# SIM4G_EC200S.net
KiCad netlist of a schematic drawn in Altium Designer
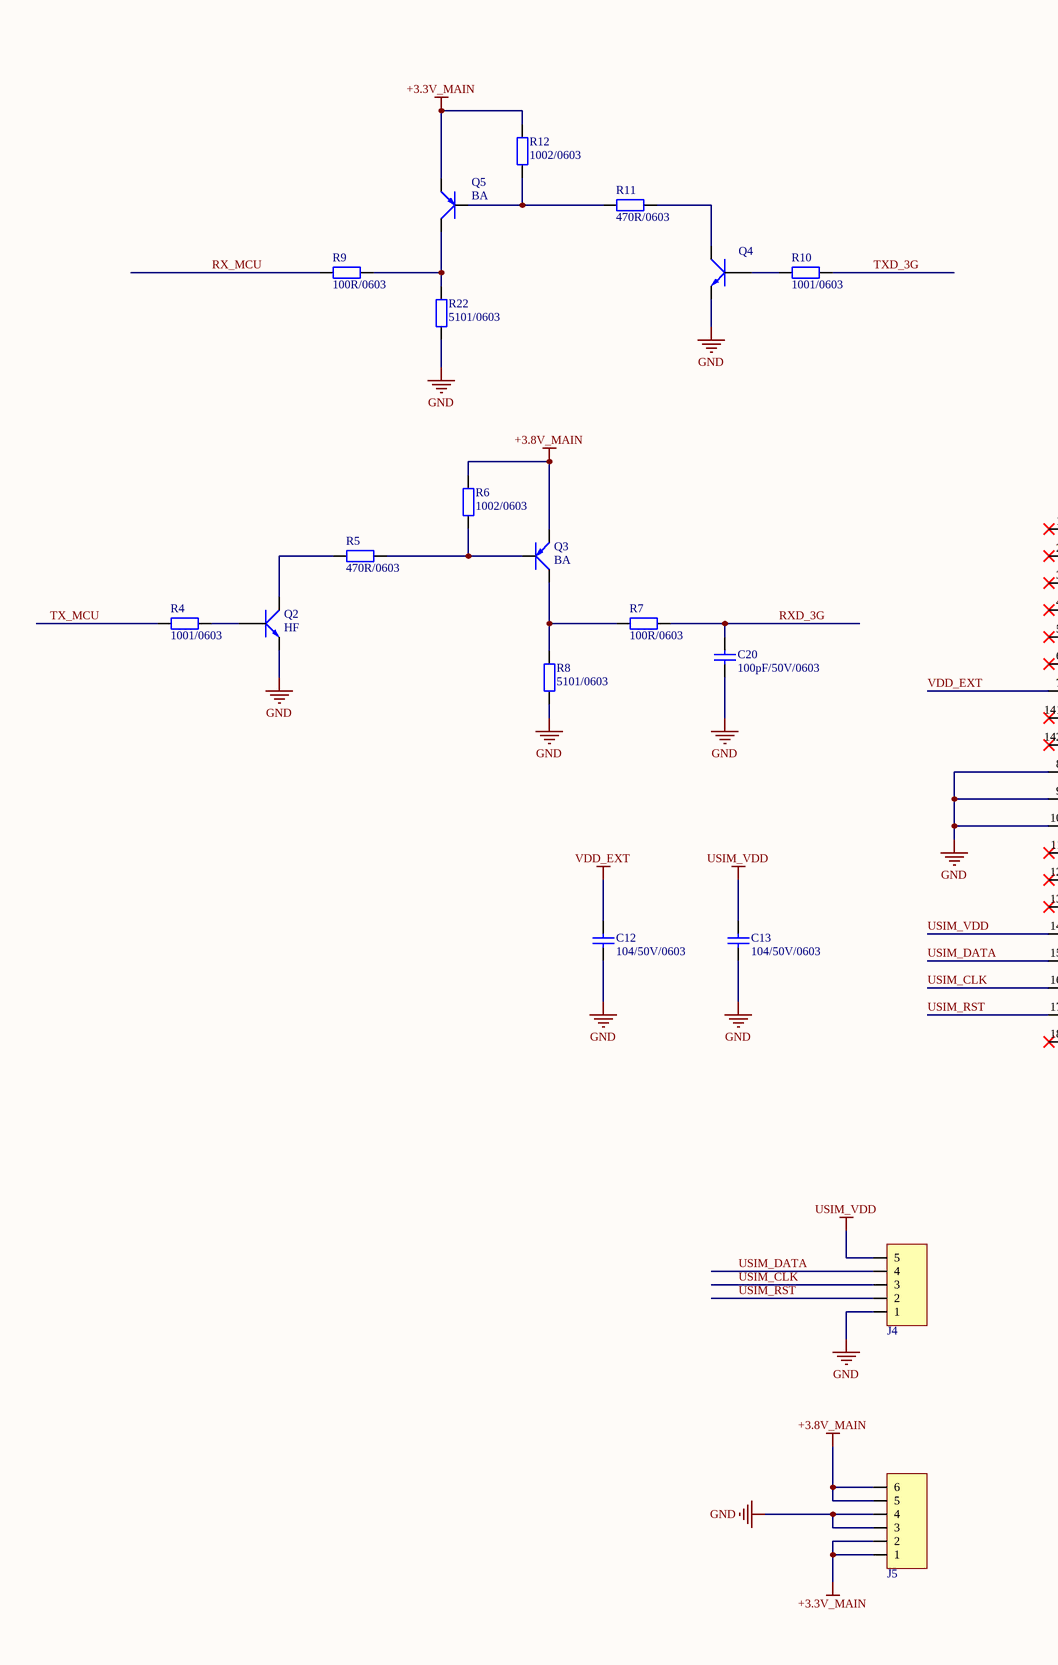
[diagram p0: SIM4G_EC200S.SchDoc, left]
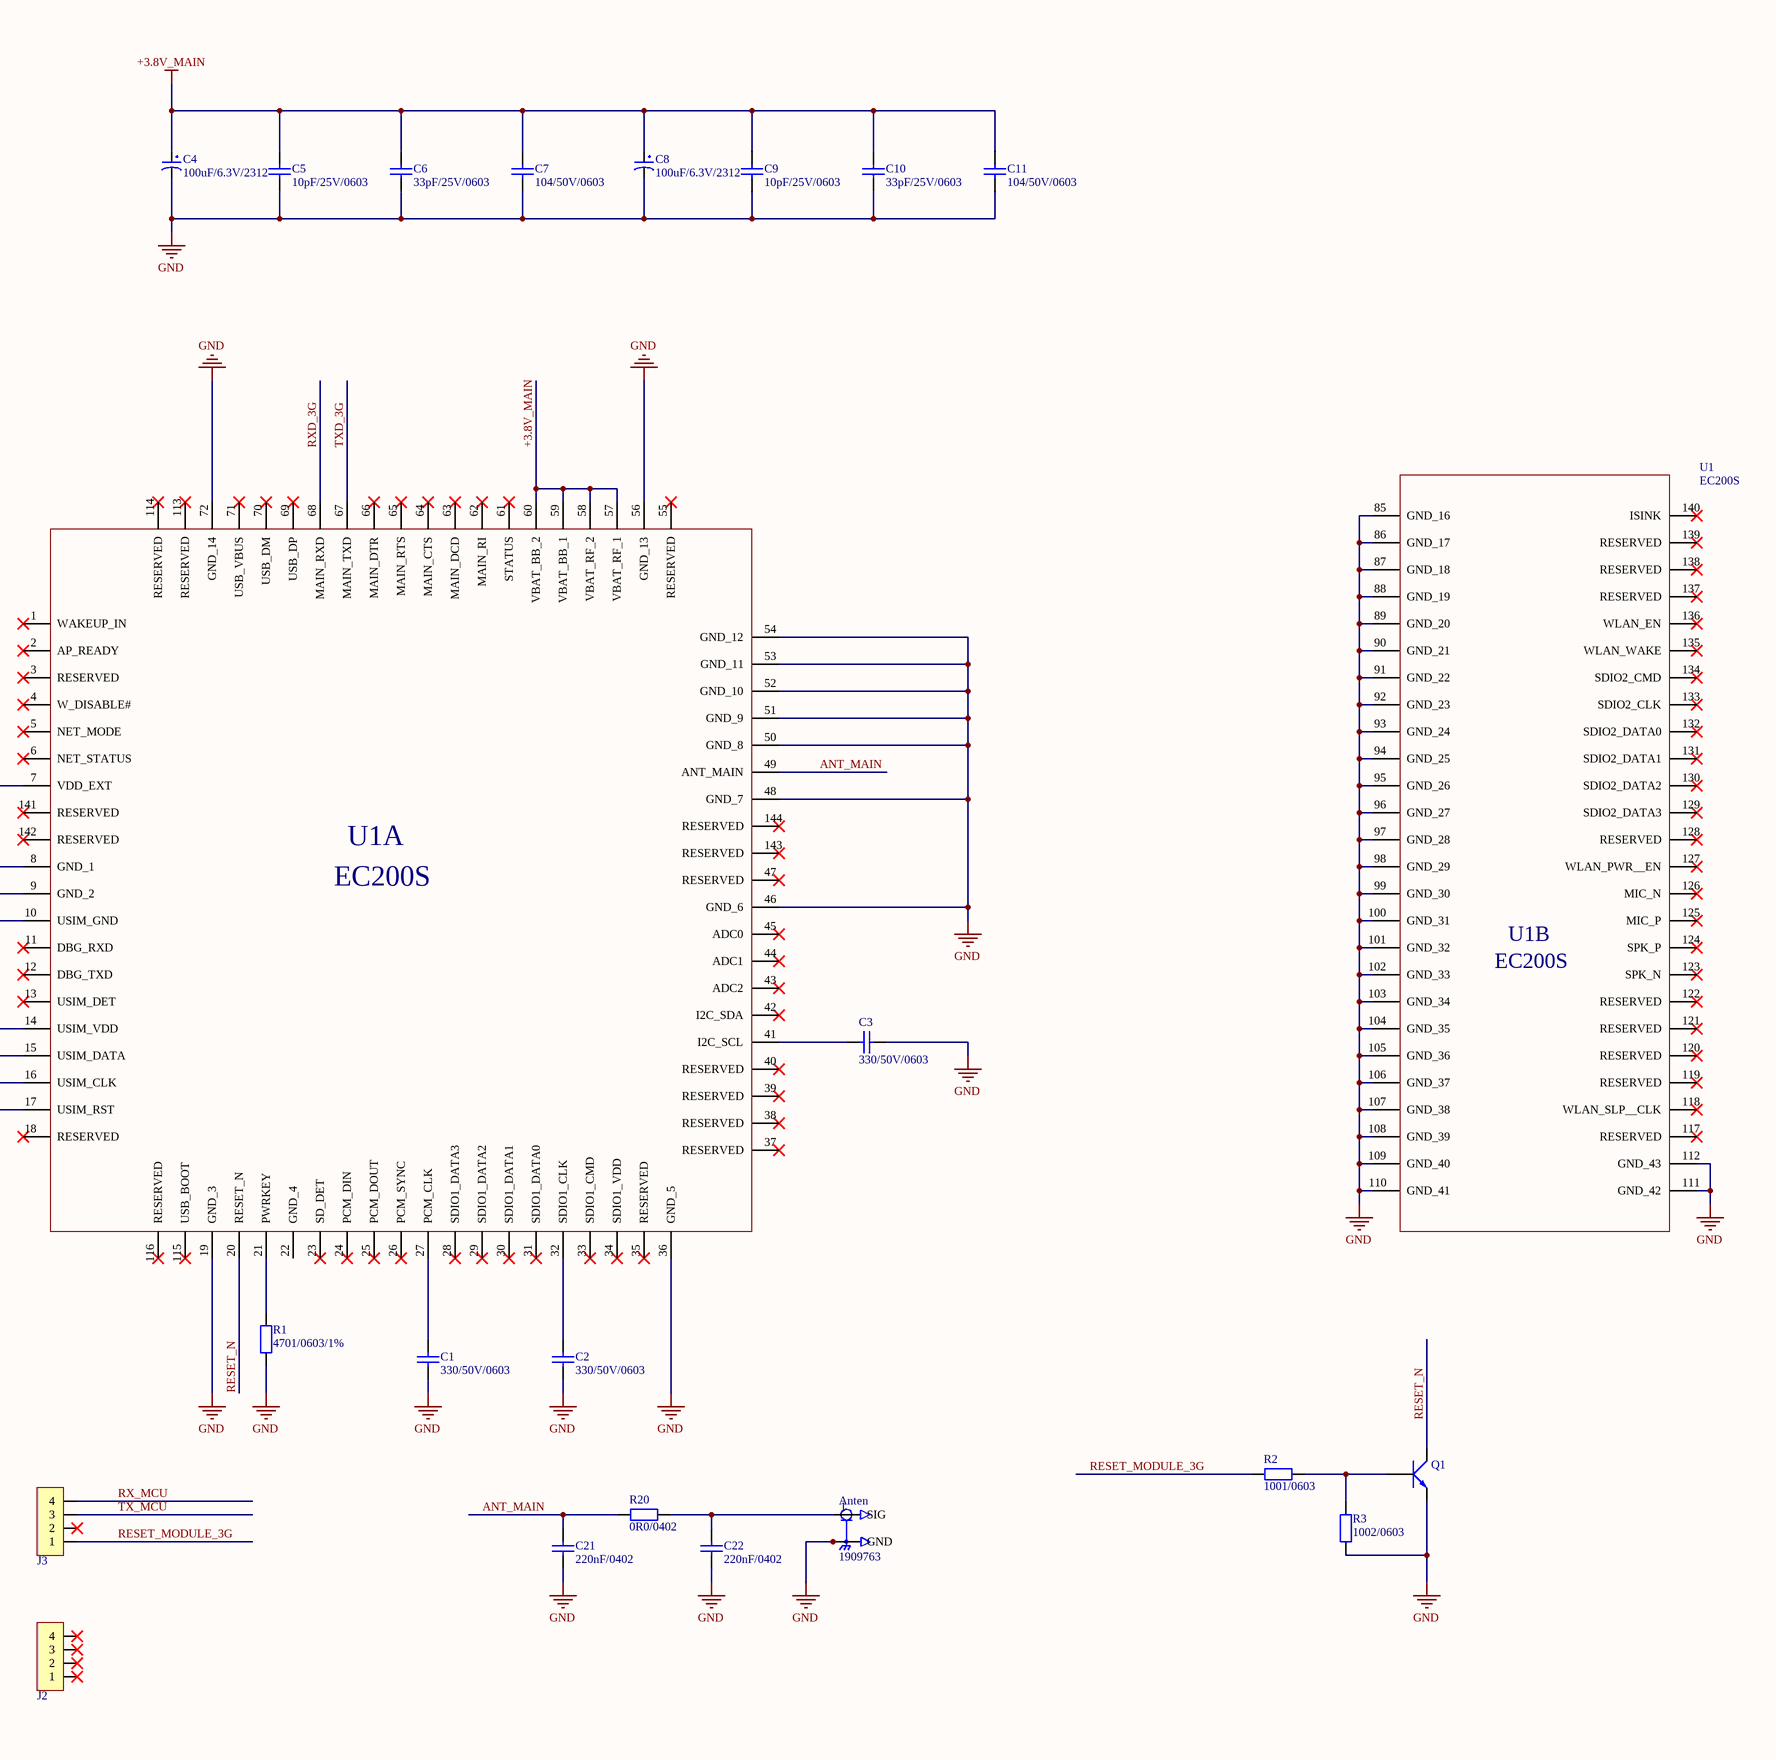
[diagram p1: SIM4G_EC200S.SchDoc, right]

(export (version "E")
  (design (tool "Eeschema 10.0.6"))
  (components
    (comp (ref "Anten")
      (value "1909763")
      (footprint "TE_1909763-1")
      (description "VAO ITEM, MINI RF HEADER")
      (fields (field (name "MP") "1909763-1"))
      (libsource (lib "Labrary_Tu_Nguon_Version2") (part "Antenna"))
    )
    (comp (ref "C1")
      (value "330/50V/0603")
      (footprint "tu 0603")
      (description "Dán")
      (libsource (lib "Altium_Lib_by_KhueNguyenCreator") (part "Tu 0603 563 16V 10%"))
    )
    (comp (ref "C2")
      (value "330/50V/0603")
      (footprint "tu 0603")
      (description "Dán")
      (libsource (lib "Altium_Lib_by_KhueNguyenCreator") (part "Tu 0603 563 16V 10%"))
    )
    (comp (ref "C3")
      (value "330/50V/0603")
      (footprint "tu 0603")
      (description "Dán")
      (libsource (lib "Altium_Lib_by_KhueNguyenCreator") (part "Tu 0603 563 16V 10%"))
    )
    (comp (ref "C4")
      (value "100uF/6.3V/2312")
      (footprint "tu tantalum smd3216")
      (description "Dán")
      (libsource (lib "Altium_Lib_by_KhueNguyenCreator") (part "Tu tantalum 10uF 16V SMD3216"))
    )
    (comp (ref "C5")
      (value "10pF/25V/0603")
      (footprint "tu 0603")
      (description "Dán")
      (libsource (lib "Altium_Lib_by_KhueNguyenCreator") (part "Tu 0603 563 16V 10%"))
    )
    (comp (ref "C6")
      (value "33pF/25V/0603")
      (footprint "tu 0603")
      (description "Dán")
      (libsource (lib "Altium_Lib_by_KhueNguyenCreator") (part "Tu 0603 563 16V 10%"))
    )
    (comp (ref "C7")
      (value "104/50V/0603")
      (footprint "tu 0603")
      (description "Dán")
      (libsource (lib "Altium_Lib_by_KhueNguyenCreator") (part "Tu 0603 563 16V 10%"))
    )
    (comp (ref "C8")
      (value "100uF/6.3V/2312")
      (footprint "tu tantalum smd3216")
      (description "Dán")
      (libsource (lib "Altium_Lib_by_KhueNguyenCreator") (part "Tu tantalum 10uF 16V SMD3216"))
    )
    (comp (ref "C9")
      (value "10pF/25V/0603")
      (footprint "tu 0603")
      (description "Dán")
      (libsource (lib "Altium_Lib_by_KhueNguyenCreator") (part "Tu 0603 563 16V 10%"))
    )
    (comp (ref "C10")
      (value "33pF/25V/0603")
      (footprint "tu 0603")
      (description "Dán")
      (libsource (lib "Altium_Lib_by_KhueNguyenCreator") (part "Tu 0603 563 16V 10%"))
    )
    (comp (ref "C11")
      (value "104/50V/0603")
      (footprint "tu 0603")
      (description "Dán")
      (libsource (lib "Altium_Lib_by_KhueNguyenCreator") (part "Tu 0603 563 16V 10%"))
    )
    (comp (ref "C12")
      (value "104/50V/0603")
      (footprint "tu 0603")
      (description "Dán")
      (libsource (lib "Altium_Lib_by_KhueNguyenCreator") (part "Tu 0603 563 16V 10%"))
    )
    (comp (ref "C13")
      (value "104/50V/0603")
      (footprint "tu 0603")
      (description "Dán")
      (libsource (lib "Altium_Lib_by_KhueNguyenCreator") (part "Tu 0603 563 16V 10%"))
    )
    (comp (ref "C20")
      (value "100pF/50V/0603")
      (footprint "tu 0603")
      (description "Dán")
      (libsource (lib "Altium_Lib_by_KhueNguyenCreator") (part "Tu 0603 563 16V 10%"))
    )
    (comp (ref "C21")
      (value "220nF/0402")
      (footprint "tu 0402")
      (description "Dán")
      (libsource (lib "Altium_Lib_by_KhueNguyenCreator") (part "Tu 0402 220nF 6.3V 20%"))
    )
    (comp (ref "C22")
      (value "220nF/0402")
      (footprint "tu 0402")
      (description "Dán")
      (libsource (lib "Altium_Lib_by_KhueNguyenCreator") (part "Tu 0402 220nF 6.3V 20%"))
    )
    (comp (ref "J2")
      (value "JP 1x4 2.54")
      (footprint "JP 1x4 DT")
      (description "Cắm")
      (libsource (lib "Altium_Lib_by_KhueNguyenCreator") (part "JP 1x4 2.54 Duc Thang"))
    )
    (comp (ref "J3")
      (value "JP 1x4 2.54")
      (footprint "JP 1x4 DT")
      (description "Cắm")
      (libsource (lib "Altium_Lib_by_KhueNguyenCreator") (part "JP 1x4 2.54 Duc Thang"))
    )
    (comp (ref "J4")
      (value "JP 1x5 2.54")
      (footprint "JP 1x5 DT")
      (description "Cắm")
      (libsource (lib "Altium_Lib_by_KhueNguyenCreator") (part "JP 1x5 2.54 Duc Thang"))
    )
    (comp (ref "J5")
      (value "JP 1x6 2.54")
      (footprint "JP 1x6 DT")
      (description "Cắm")
      (libsource (lib "Altium_Lib_by_KhueNguyenCreator") (part "JP 1x6 2.54 Duc Thang"))
    )
    (comp (ref "Q1")
      (value "HF")
      (footprint "SOT23")
      (description "NPN transistor")
      (libsource (lib "Altium_Lib_by_KhueNguyenCreator") (part "C1815 HF SMD"))
    )
    (comp (ref "Q2")
      (value "HF")
      (footprint "SOT23")
      (description "NPN transistor")
      (libsource (lib "Altium_Lib_by_KhueNguyenCreator") (part "C1815 HF SMD"))
    )
    (comp (ref "Q3")
      (value "BA")
      (footprint "SOT23")
      (description "PMBT3906,235\r\nMMBT4403/SOT_0")
      (libsource (lib "Altium_Lib_by_KhueNguyenCreator") (part "A1015 BA SMD"))
    )
    (comp (ref "Q4")
      (value "HF")
      (footprint "SOT23")
      (description "NPN transistor")
      (libsource (lib "Altium_Lib_by_KhueNguyenCreator") (part "C1815 HF SMD"))
    )
    (comp (ref "Q5")
      (value "BA")
      (footprint "SOT23")
      (description "PNP 600mW, ECB")
      (libsource (lib "Altium_Lib_by_KhueNguyenCreator") (part "A1015 BA SMD"))
    )
    (comp (ref "R1")
      (value "4701/0603/1%")
      (footprint "tro smd 0603")
      (description "Dán")
      (libsource (lib "Altium_Lib_by_KhueNguyenCreator") (part "Tro 0603 5% 510R"))
    )
    (comp (ref "R2")
      (value "1001/0603")
      (footprint "tro smd 0603")
      (description "Dán")
      (libsource (lib "Altium_Lib_by_KhueNguyenCreator") (part "Tro 0603 5% 510R"))
    )
    (comp (ref "R3")
      (value "1002/0603")
      (footprint "tro smd 0603")
      (description "Dán")
      (libsource (lib "Altium_Lib_by_KhueNguyenCreator") (part "Tro 0603 5% 510R"))
    )
    (comp (ref "R4")
      (value "1001/0603")
      (footprint "tro smd 0603")
      (description "Dán")
      (libsource (lib "Altium_Lib_by_KhueNguyenCreator") (part "Tro 0603 5% 510R"))
    )
    (comp (ref "R5")
      (value "470R/0603")
      (footprint "tro smd 0603")
      (description "Dán")
      (libsource (lib "Altium_Lib_by_KhueNguyenCreator") (part "Tro 0603 5% 510R"))
    )
    (comp (ref "R6")
      (value "1002/0603")
      (footprint "tro smd 0603")
      (description "Dán")
      (libsource (lib "Altium_Lib_by_KhueNguyenCreator") (part "Tro 0603 5% 510R"))
    )
    (comp (ref "R7")
      (value "100R/0603")
      (footprint "tro smd 0603")
      (description "Dán")
      (libsource (lib "Altium_Lib_by_KhueNguyenCreator") (part "Tro 0603 5% 510R"))
    )
    (comp (ref "R8")
      (value "5101/0603")
      (footprint "tro smd 0603")
      (description "Dán")
      (libsource (lib "Altium_Lib_by_KhueNguyenCreator") (part "Tro 0603 5% 510R"))
    )
    (comp (ref "R9")
      (value "100R/0603")
      (footprint "tro smd 0603")
      (description "Dán")
      (libsource (lib "Altium_Lib_by_KhueNguyenCreator") (part "Tro 0603 5% 510R"))
    )
    (comp (ref "R10")
      (value "1001/0603")
      (footprint "tro smd 0603")
      (description "Dán")
      (libsource (lib "Altium_Lib_by_KhueNguyenCreator") (part "Tro 0603 5% 510R"))
    )
    (comp (ref "R11")
      (value "470R/0603")
      (footprint "tro smd 0603")
      (description "Dán")
      (libsource (lib "Altium_Lib_by_KhueNguyenCreator") (part "Tro 0603 5% 510R"))
    )
    (comp (ref "R12")
      (value "1002/0603")
      (footprint "tro smd 0603")
      (description "Dán")
      (libsource (lib "Altium_Lib_by_KhueNguyenCreator") (part "Tro 0603 5% 510R"))
    )
    (comp (ref "R20")
      (value "0R0/0402")
      (footprint "tro smd 0603")
      (description "Dán")
      (libsource (lib "Altium_Lib_by_KhueNguyenCreator") (part "Tro 0603 5% 510R"))
    )
    (comp (ref "R22")
      (value "5101/0603")
      (footprint "tro smd 0603")
      (description "Dán")
      (libsource (lib "Altium_Lib_by_KhueNguyenCreator") (part "Tro 0603 5% 510R"))
    )
    (comp (ref "U1")
      (value "EC200S")
      (footprint "EC200U")
      (description "GMS/4G-LTE")
      (libsource (lib "Labrary_Tu_Nguon_Version2") (part "EC200S"))
    )
  )
  (nets
    (net (code "1") (name "+3.3V_MAIN") (class "Default")
      (node (ref "J5") (pin "1") (pinfunction "1_1") (pintype "passive"))
      (node (ref "J5") (pin "2") (pinfunction "2_2") (pintype "passive"))
      (node (ref "Q5") (pin "2") (pinfunction "E_2") (pintype "passive"))
      (node (ref "R12") (pin "1") (pinfunction "1_1") (pintype "passive"))
    )
    (net (code "2") (name "+3.8V_MAIN") (class "Default")
      (node (ref "C10") (pin "1") (pinfunction "1_1") (pintype "passive"))
      (node (ref "C11") (pin "1") (pinfunction "1_1") (pintype "passive"))
      (node (ref "C4") (pin "1") (pinfunction "1_1") (pintype "passive"))
      (node (ref "C5") (pin "1") (pinfunction "1_1") (pintype "passive"))
      (node (ref "C6") (pin "1") (pinfunction "1_1") (pintype "passive"))
      (node (ref "C7") (pin "1") (pinfunction "1_1") (pintype "passive"))
      (node (ref "C8") (pin "1") (pinfunction "1_1") (pintype "passive"))
      (node (ref "C9") (pin "1") (pinfunction "1_1") (pintype "passive"))
      (node (ref "J5") (pin "5") (pinfunction "5_5") (pintype "passive"))
      (node (ref "J5") (pin "6") (pinfunction "6_6") (pintype "passive"))
      (node (ref "Q3") (pin "2") (pinfunction "E_2") (pintype "passive"))
      (node (ref "R6") (pin "1") (pinfunction "1_1") (pintype "passive"))
      (node (ref "U1") (pin "57") (pinfunction "VBAT_RF_1_57") (pintype "passive"))
      (node (ref "U1") (pin "58") (pinfunction "VBAT_RF_2_58") (pintype "passive"))
      (node (ref "U1") (pin "59") (pinfunction "VBAT_BB_1_59") (pintype "passive"))
      (node (ref "U1") (pin "60") (pinfunction "VBAT_BB_2_60") (pintype "passive"))
    )
    (net (code "3") (name "/ANT_MAIN") (class "Default")
      (node (ref "C21") (pin "2") (pinfunction "2_2") (pintype "passive"))
      (node (ref "R20") (pin "1") (pinfunction "1_1") (pintype "passive"))
      (node (ref "U1") (pin "49") (pinfunction "ANT_MAIN_49") (pintype "passive"))
    )
    (net (code "4") (name "/RESET_MODULE_3G") (class "Default")
      (node (ref "J3") (pin "1") (pinfunction "1_1") (pintype "passive"))
      (node (ref "R2") (pin "2") (pinfunction "2_2") (pintype "passive"))
    )
    (net (code "5") (name "/RESET_N") (class "Default")
      (node (ref "Q1") (pin "3") (pinfunction "C_3") (pintype "passive"))
      (node (ref "U1") (pin "20") (pinfunction "RESET_N_20") (pintype "passive"))
    )
    (net (code "6") (name "/RXD_3G") (class "Default")
      (node (ref "C20") (pin "1") (pinfunction "1_1") (pintype "passive"))
      (node (ref "R7") (pin "1") (pinfunction "1_1") (pintype "passive"))
      (node (ref "U1") (pin "68") (pinfunction "MAIN_RXD_68") (pintype "passive"))
    )
    (net (code "7") (name "/RX_MCU") (class "Default")
      (node (ref "J3") (pin "4") (pinfunction "4_4") (pintype "passive"))
      (node (ref "R9") (pin "1") (pinfunction "1_1") (pintype "passive"))
    )
    (net (code "8") (name "/TXD_3G") (class "Default")
      (node (ref "R10") (pin "2") (pinfunction "2_2") (pintype "passive"))
      (node (ref "U1") (pin "67") (pinfunction "MAIN_TXD_67") (pintype "passive"))
    )
    (net (code "9") (name "/TX_MCU") (class "Default")
      (node (ref "J3") (pin "3") (pinfunction "3_3") (pintype "passive"))
      (node (ref "R4") (pin "2") (pinfunction "2_2") (pintype "passive"))
    )
    (net (code "10") (name "/USIM_CLK") (class "Default")
      (node (ref "J4") (pin "3") (pinfunction "3_3") (pintype "passive"))
      (node (ref "U1") (pin "16") (pinfunction "USIM_CLK_16") (pintype "passive"))
    )
    (net (code "11") (name "/USIM_DATA") (class "Default")
      (node (ref "J4") (pin "4") (pinfunction "4_4") (pintype "passive"))
      (node (ref "U1") (pin "15") (pinfunction "USIM_DATA_15") (pintype "passive"))
    )
    (net (code "12") (name "/USIM_RST") (class "Default")
      (node (ref "J4") (pin "2") (pinfunction "2_2") (pintype "passive"))
      (node (ref "U1") (pin "17") (pinfunction "USIM_RST_17") (pintype "passive"))
    )
    (net (code "13") (name "GND") (class "Default")
      (node (ref "Anten") (pin "2") (pinfunction "GND_2") (pintype "passive"))
      (node (ref "Anten") (pin "3") (pinfunction "GND_3") (pintype "passive"))
      (node (ref "C1") (pin "2") (pinfunction "2_2") (pintype "passive"))
      (node (ref "C10") (pin "2") (pinfunction "2_2") (pintype "passive"))
      (node (ref "C11") (pin "2") (pinfunction "2_2") (pintype "passive"))
      (node (ref "C12") (pin "2") (pinfunction "2_2") (pintype "passive"))
      (node (ref "C13") (pin "2") (pinfunction "2_2") (pintype "passive"))
      (node (ref "C2") (pin "2") (pinfunction "2_2") (pintype "passive"))
      (node (ref "C20") (pin "2") (pinfunction "2_2") (pintype "passive"))
      (node (ref "C21") (pin "1") (pinfunction "1_1") (pintype "passive"))
      (node (ref "C22") (pin "1") (pinfunction "1_1") (pintype "passive"))
      (node (ref "C3") (pin "2") (pinfunction "2_2") (pintype "passive"))
      (node (ref "C4") (pin "2") (pinfunction "2_2") (pintype "passive"))
      (node (ref "C5") (pin "2") (pinfunction "2_2") (pintype "passive"))
      (node (ref "C6") (pin "2") (pinfunction "2_2") (pintype "passive"))
      (node (ref "C7") (pin "2") (pinfunction "2_2") (pintype "passive"))
      (node (ref "C8") (pin "2") (pinfunction "2_2") (pintype "passive"))
      (node (ref "C9") (pin "2") (pinfunction "2_2") (pintype "passive"))
      (node (ref "J4") (pin "1") (pinfunction "1_1") (pintype "passive"))
      (node (ref "J5") (pin "3") (pinfunction "3_3") (pintype "passive"))
      (node (ref "J5") (pin "4") (pinfunction "4_4") (pintype "passive"))
      (node (ref "Q1") (pin "2") (pinfunction "E_2") (pintype "passive"))
      (node (ref "Q2") (pin "2") (pinfunction "E_2") (pintype "passive"))
      (node (ref "Q4") (pin "2") (pinfunction "E_2") (pintype "passive"))
      (node (ref "R1") (pin "1") (pinfunction "1_1") (pintype "passive"))
      (node (ref "R22") (pin "2") (pinfunction "2_2") (pintype "passive"))
      (node (ref "R3") (pin "2") (pinfunction "2_2") (pintype "passive"))
      (node (ref "R8") (pin "2") (pinfunction "2_2") (pintype "passive"))
      (node (ref "U1") (pin "10") (pinfunction "USIM_GND_10") (pintype "passive"))
      (node (ref "U1") (pin "100") (pinfunction "GND_31_100") (pintype "passive"))
      (node (ref "U1") (pin "101") (pinfunction "GND_32_101") (pintype "passive"))
      (node (ref "U1") (pin "102") (pinfunction "GND_33_102") (pintype "passive"))
      (node (ref "U1") (pin "103") (pinfunction "GND_34_103") (pintype "passive"))
      (node (ref "U1") (pin "104") (pinfunction "GND_35_104") (pintype "passive"))
      (node (ref "U1") (pin "105") (pinfunction "GND_36_105") (pintype "passive"))
      (node (ref "U1") (pin "106") (pinfunction "GND_37_106") (pintype "passive"))
      (node (ref "U1") (pin "107") (pinfunction "GND_38_107") (pintype "passive"))
      (node (ref "U1") (pin "108") (pinfunction "GND_39_108") (pintype "passive"))
      (node (ref "U1") (pin "109") (pinfunction "GND_40_109") (pintype "passive"))
      (node (ref "U1") (pin "110") (pinfunction "GND_41_110") (pintype "passive"))
      (node (ref "U1") (pin "111") (pinfunction "GND_42_111") (pintype "passive"))
      (node (ref "U1") (pin "112") (pinfunction "GND_43_112") (pintype "passive"))
      (node (ref "U1") (pin "19") (pinfunction "GND_3_19") (pintype "passive"))
      (node (ref "U1") (pin "36") (pinfunction "GND_5_36") (pintype "passive"))
      (node (ref "U1") (pin "46") (pinfunction "GND_6_46") (pintype "passive"))
      (node (ref "U1") (pin "48") (pinfunction "GND_7_48") (pintype "passive"))
      (node (ref "U1") (pin "50") (pinfunction "GND_8_50") (pintype "passive"))
      (node (ref "U1") (pin "51") (pinfunction "GND_9_51") (pintype "passive"))
      (node (ref "U1") (pin "52") (pinfunction "GND_10_52") (pintype "passive"))
      (node (ref "U1") (pin "53") (pinfunction "GND_11_53") (pintype "passive"))
      (node (ref "U1") (pin "54") (pinfunction "GND_12_54") (pintype "passive"))
      (node (ref "U1") (pin "56") (pinfunction "GND_13_56") (pintype "passive"))
      (node (ref "U1") (pin "72") (pinfunction "GND_14_72") (pintype "passive"))
      (node (ref "U1") (pin "8") (pinfunction "GND_1_8") (pintype "passive"))
      (node (ref "U1") (pin "85") (pinfunction "GND_16_85") (pintype "passive"))
      (node (ref "U1") (pin "86") (pinfunction "GND_17_86") (pintype "passive"))
      (node (ref "U1") (pin "87") (pinfunction "GND_18_87") (pintype "passive"))
      (node (ref "U1") (pin "88") (pinfunction "GND_19_88") (pintype "passive"))
      (node (ref "U1") (pin "89") (pinfunction "GND_20_89") (pintype "passive"))
      (node (ref "U1") (pin "9") (pinfunction "GND_2_9") (pintype "passive"))
      (node (ref "U1") (pin "90") (pinfunction "GND_21_90") (pintype "passive"))
      (node (ref "U1") (pin "91") (pinfunction "GND_22_91") (pintype "passive"))
      (node (ref "U1") (pin "92") (pinfunction "GND_23_92") (pintype "passive"))
      (node (ref "U1") (pin "93") (pinfunction "GND_24_93") (pintype "passive"))
      (node (ref "U1") (pin "94") (pinfunction "GND_25_94") (pintype "passive"))
      (node (ref "U1") (pin "95") (pinfunction "GND_26_95") (pintype "passive"))
      (node (ref "U1") (pin "96") (pinfunction "GND_27_96") (pintype "passive"))
      (node (ref "U1") (pin "97") (pinfunction "GND_28_97") (pintype "passive"))
      (node (ref "U1") (pin "98") (pinfunction "GND_29_98") (pintype "passive"))
      (node (ref "U1") (pin "99") (pinfunction "GND_30_99") (pintype "passive"))
    )
    (net (code "14") (name "Net-(Anten-SIG)") (class "Default")
      (node (ref "Anten") (pin "1") (pinfunction "SIG_1") (pintype "passive"))
      (node (ref "C22") (pin "2") (pinfunction "2_2") (pintype "passive"))
      (node (ref "R20") (pin "2") (pinfunction "2_2") (pintype "passive"))
    )
    (net (code "15") (name "Net-(Q1-B)") (class "Default")
      (node (ref "Q1") (pin "1") (pinfunction "B_1") (pintype "passive"))
      (node (ref "R2") (pin "1") (pinfunction "1_1") (pintype "passive"))
      (node (ref "R3") (pin "1") (pinfunction "1_1") (pintype "passive"))
    )
    (net (code "16") (name "Net-(Q2-B)") (class "Default")
      (node (ref "Q2") (pin "1") (pinfunction "B_1") (pintype "passive"))
      (node (ref "R4") (pin "1") (pinfunction "1_1") (pintype "passive"))
    )
    (net (code "17") (name "Net-(Q2-C)") (class "Default")
      (node (ref "Q2") (pin "3") (pinfunction "C_3") (pintype "passive"))
      (node (ref "R5") (pin "2") (pinfunction "2_2") (pintype "passive"))
    )
    (net (code "18") (name "Net-(Q3-B)") (class "Default")
      (node (ref "Q3") (pin "1") (pinfunction "B_1") (pintype "passive"))
      (node (ref "R5") (pin "1") (pinfunction "1_1") (pintype "passive"))
      (node (ref "R6") (pin "2") (pinfunction "2_2") (pintype "passive"))
    )
    (net (code "19") (name "Net-(Q3-C)") (class "Default")
      (node (ref "Q3") (pin "3") (pinfunction "C_3") (pintype "passive"))
      (node (ref "R7") (pin "2") (pinfunction "2_2") (pintype "passive"))
      (node (ref "R8") (pin "1") (pinfunction "1_1") (pintype "passive"))
    )
    (net (code "20") (name "Net-(Q4-B)") (class "Default")
      (node (ref "Q4") (pin "1") (pinfunction "B_1") (pintype "passive"))
      (node (ref "R10") (pin "1") (pinfunction "1_1") (pintype "passive"))
    )
    (net (code "21") (name "Net-(Q4-C)") (class "Default")
      (node (ref "Q4") (pin "3") (pinfunction "C_3") (pintype "passive"))
      (node (ref "R11") (pin "2") (pinfunction "2_2") (pintype "passive"))
    )
    (net (code "22") (name "Net-(Q5-B)") (class "Default")
      (node (ref "Q5") (pin "1") (pinfunction "B_1") (pintype "passive"))
      (node (ref "R11") (pin "1") (pinfunction "1_1") (pintype "passive"))
      (node (ref "R12") (pin "2") (pinfunction "2_2") (pintype "passive"))
    )
    (net (code "23") (name "Net-(Q5-C)") (class "Default")
      (node (ref "Q5") (pin "3") (pinfunction "C_3") (pintype "passive"))
      (node (ref "R22") (pin "1") (pinfunction "1_1") (pintype "passive"))
      (node (ref "R9") (pin "2") (pinfunction "2_2") (pintype "passive"))
    )
    (net (code "24") (name "Net-(U1-I2C_SCL)") (class "Default")
      (node (ref "C3") (pin "1") (pinfunction "1_1") (pintype "passive"))
      (node (ref "U1") (pin "41") (pinfunction "I2C_SCL_41") (pintype "passive"))
    )
    (net (code "25") (name "Net-(U1-PCM_CLK)") (class "Default")
      (node (ref "C1") (pin "1") (pinfunction "1_1") (pintype "passive"))
      (node (ref "U1") (pin "27") (pinfunction "PCM_CLK_27") (pintype "passive"))
    )
    (net (code "26") (name "Net-(U1-PWRKEY)") (class "Default")
      (node (ref "R1") (pin "2") (pinfunction "2_2") (pintype "passive"))
      (node (ref "U1") (pin "21") (pinfunction "PWRKEY_21") (pintype "passive"))
    )
    (net (code "27") (name "Net-(U1-SDIO1_CLK)") (class "Default")
      (node (ref "C2") (pin "1") (pinfunction "1_1") (pintype "passive"))
      (node (ref "U1") (pin "32") (pinfunction "SDIO1_CLK_32") (pintype "passive"))
    )
    (net (code "28") (name "USIM_VDD") (class "Default")
      (node (ref "C13") (pin "1") (pinfunction "1_1") (pintype "passive"))
      (node (ref "J4") (pin "5") (pinfunction "5_5") (pintype "passive"))
      (node (ref "U1") (pin "14") (pinfunction "USIM_VDD_14") (pintype "passive"))
    )
    (net (code "29") (name "VDD_EXT") (class "Default")
      (node (ref "C12") (pin "1") (pinfunction "1_1") (pintype "passive"))
      (node (ref "U1") (pin "7") (pinfunction "VDD_EXT_7") (pintype "passive"))
    )
    (net (code "30") (name "unconnected-(J2-Pad1)") (class "Default")
      (node (ref "J2") (pin "1") (pinfunction "1_1") (pintype "passive+no_connect"))
    )
    (net (code "31") (name "unconnected-(J2-Pad2)") (class "Default")
      (node (ref "J2") (pin "2") (pinfunction "2_2") (pintype "passive+no_connect"))
    )
    (net (code "32") (name "unconnected-(J2-Pad3)") (class "Default")
      (node (ref "J2") (pin "3") (pinfunction "3_3") (pintype "passive+no_connect"))
    )
    (net (code "33") (name "unconnected-(J2-Pad4)") (class "Default")
      (node (ref "J2") (pin "4") (pinfunction "4_4") (pintype "passive+no_connect"))
    )
    (net (code "34") (name "unconnected-(J3-Pad2)") (class "Default")
      (node (ref "J3") (pin "2") (pinfunction "2_2") (pintype "passive+no_connect"))
    )
    (net (code "35") (name "unconnected-(U1-ADC0-Pad45)") (class "Default")
      (node (ref "U1") (pin "45") (pinfunction "ADC0_45") (pintype "passive+no_connect"))
    )
    (net (code "36") (name "unconnected-(U1-ADC1-Pad44)") (class "Default")
      (node (ref "U1") (pin "44") (pinfunction "ADC1_44") (pintype "passive+no_connect"))
    )
    (net (code "37") (name "unconnected-(U1-ADC2-Pad43)") (class "Default")
      (node (ref "U1") (pin "43") (pinfunction "ADC2_43") (pintype "passive+no_connect"))
    )
    (net (code "38") (name "unconnected-(U1-AP_READY-Pad2)") (class "Default")
      (node (ref "U1") (pin "2") (pinfunction "AP_READY_2") (pintype "passive+no_connect"))
    )
    (net (code "39") (name "unconnected-(U1-DBG_RXD-Pad11)") (class "Default")
      (node (ref "U1") (pin "11") (pinfunction "DBG_RXD_11") (pintype "passive+no_connect"))
    )
    (net (code "40") (name "unconnected-(U1-DBG_TXD-Pad12)") (class "Default")
      (node (ref "U1") (pin "12") (pinfunction "DBG_TXD_12") (pintype "passive+no_connect"))
    )
    (net (code "41") (name "unconnected-(U1-GND_4-Pad22)") (class "Default")
      (node (ref "U1") (pin "22") (pinfunction "GND_4_22") (pintype "passive"))
    )
    (net (code "42") (name "unconnected-(U1-I2C_SDA-Pad42)") (class "Default")
      (node (ref "U1") (pin "42") (pinfunction "I2C_SDA_42") (pintype "passive+no_connect"))
    )
    (net (code "43") (name "unconnected-(U1-ISINK-Pad140)") (class "Default")
      (node (ref "U1") (pin "140") (pinfunction "ISINK_140") (pintype "passive+no_connect"))
    )
    (net (code "44") (name "unconnected-(U1-MAIN_CTS-Pad64)") (class "Default")
      (node (ref "U1") (pin "64") (pinfunction "MAIN_CTS_64") (pintype "passive+no_connect"))
    )
    (net (code "45") (name "unconnected-(U1-MAIN_DCD-Pad63)") (class "Default")
      (node (ref "U1") (pin "63") (pinfunction "MAIN_DCD_63") (pintype "passive+no_connect"))
    )
    (net (code "46") (name "unconnected-(U1-MAIN_DTR-Pad66)") (class "Default")
      (node (ref "U1") (pin "66") (pinfunction "MAIN_DTR_66") (pintype "passive+no_connect"))
    )
    (net (code "47") (name "unconnected-(U1-MAIN_RI-Pad62)") (class "Default")
      (node (ref "U1") (pin "62") (pinfunction "MAIN_RI_62") (pintype "passive+no_connect"))
    )
    (net (code "48") (name "unconnected-(U1-MAIN_RTS-Pad65)") (class "Default")
      (node (ref "U1") (pin "65") (pinfunction "MAIN_RTS_65") (pintype "passive+no_connect"))
    )
    (net (code "49") (name "unconnected-(U1-MIC_N-Pad126)") (class "Default")
      (node (ref "U1") (pin "126") (pinfunction "MIC_N_126") (pintype "passive+no_connect"))
    )
    (net (code "50") (name "unconnected-(U1-MIC_P-Pad125)") (class "Default")
      (node (ref "U1") (pin "125") (pinfunction "MIC_P_125") (pintype "passive+no_connect"))
    )
    (net (code "51") (name "unconnected-(U1-NET_MODE-Pad5)") (class "Default")
      (node (ref "U1") (pin "5") (pinfunction "NET_MODE_5") (pintype "passive+no_connect"))
    )
    (net (code "52") (name "unconnected-(U1-NET_STATUS-Pad6)") (class "Default")
      (node (ref "U1") (pin "6") (pinfunction "NET_STATUS_6") (pintype "passive+no_connect"))
    )
    (net (code "53") (name "unconnected-(U1-PCM_DIN-Pad24)") (class "Default")
      (node (ref "U1") (pin "24") (pinfunction "PCM_DIN_24") (pintype "passive+no_connect"))
    )
    (net (code "54") (name "unconnected-(U1-PCM_DOUT-Pad25)") (class "Default")
      (node (ref "U1") (pin "25") (pinfunction "PCM_DOUT_25") (pintype "passive+no_connect"))
    )
    (net (code "55") (name "unconnected-(U1-PCM_SYNC-Pad26)") (class "Default")
      (node (ref "U1") (pin "26") (pinfunction "PCM_SYNC_26") (pintype "passive+no_connect"))
    )
    (net (code "56") (name "unconnected-(U1-RESERVED-Pad3)") (class "Default")
      (node (ref "U1") (pin "3") (pinfunction "RESERVED_3") (pintype "passive+no_connect"))
    )
    (net (code "57") (name "unconnected-(U1-RESERVED-Pad18)") (class "Default")
      (node (ref "U1") (pin "18") (pinfunction "RESERVED_18") (pintype "passive+no_connect"))
    )
    (net (code "58") (name "unconnected-(U1-RESERVED-Pad35)") (class "Default")
      (node (ref "U1") (pin "35") (pinfunction "RESERVED_35") (pintype "passive+no_connect"))
    )
    (net (code "59") (name "unconnected-(U1-RESERVED-Pad37)") (class "Default")
      (node (ref "U1") (pin "37") (pinfunction "RESERVED_37") (pintype "passive+no_connect"))
    )
    (net (code "60") (name "unconnected-(U1-RESERVED-Pad38)") (class "Default")
      (node (ref "U1") (pin "38") (pinfunction "RESERVED_38") (pintype "passive+no_connect"))
    )
    (net (code "61") (name "unconnected-(U1-RESERVED-Pad39)") (class "Default")
      (node (ref "U1") (pin "39") (pinfunction "RESERVED_39") (pintype "passive+no_connect"))
    )
    (net (code "62") (name "unconnected-(U1-RESERVED-Pad40)") (class "Default")
      (node (ref "U1") (pin "40") (pinfunction "RESERVED_40") (pintype "passive+no_connect"))
    )
    (net (code "63") (name "unconnected-(U1-RESERVED-Pad47)") (class "Default")
      (node (ref "U1") (pin "47") (pinfunction "RESERVED_47") (pintype "passive+no_connect"))
    )
    (net (code "64") (name "unconnected-(U1-RESERVED-Pad55)") (class "Default")
      (node (ref "U1") (pin "55") (pinfunction "RESERVED_55") (pintype "passive+no_connect"))
    )
    (net (code "65") (name "unconnected-(U1-RESERVED-Pad113)") (class "Default")
      (node (ref "U1") (pin "113") (pinfunction "RESERVED_113") (pintype "passive+no_connect"))
    )
    (net (code "66") (name "unconnected-(U1-RESERVED-Pad114)") (class "Default")
      (node (ref "U1") (pin "114") (pinfunction "RESERVED_114") (pintype "passive+no_connect"))
    )
    (net (code "67") (name "unconnected-(U1-RESERVED-Pad116)") (class "Default")
      (node (ref "U1") (pin "116") (pinfunction "RESERVED_116") (pintype "passive+no_connect"))
    )
    (net (code "68") (name "unconnected-(U1-RESERVED-Pad117)") (class "Default")
      (node (ref "U1") (pin "117") (pinfunction "RESERVED_117") (pintype "passive+no_connect"))
    )
    (net (code "69") (name "unconnected-(U1-RESERVED-Pad119)") (class "Default")
      (node (ref "U1") (pin "119") (pinfunction "RESERVED_119") (pintype "passive+no_connect"))
    )
    (net (code "70") (name "unconnected-(U1-RESERVED-Pad120)") (class "Default")
      (node (ref "U1") (pin "120") (pinfunction "RESERVED_120") (pintype "passive+no_connect"))
    )
    (net (code "71") (name "unconnected-(U1-RESERVED-Pad121)") (class "Default")
      (node (ref "U1") (pin "121") (pinfunction "RESERVED_121") (pintype "passive+no_connect"))
    )
    (net (code "72") (name "unconnected-(U1-RESERVED-Pad122)") (class "Default")
      (node (ref "U1") (pin "122") (pinfunction "RESERVED_122") (pintype "passive+no_connect"))
    )
    (net (code "73") (name "unconnected-(U1-RESERVED-Pad128)") (class "Default")
      (node (ref "U1") (pin "128") (pinfunction "RESERVED_128") (pintype "passive+no_connect"))
    )
    (net (code "74") (name "unconnected-(U1-RESERVED-Pad137)") (class "Default")
      (node (ref "U1") (pin "137") (pinfunction "RESERVED_137") (pintype "passive+no_connect"))
    )
    (net (code "75") (name "unconnected-(U1-RESERVED-Pad138)") (class "Default")
      (node (ref "U1") (pin "138") (pinfunction "RESERVED_138") (pintype "passive+no_connect"))
    )
    (net (code "76") (name "unconnected-(U1-RESERVED-Pad139)") (class "Default")
      (node (ref "U1") (pin "139") (pinfunction "RESERVED_139") (pintype "passive+no_connect"))
    )
    (net (code "77") (name "unconnected-(U1-RESERVED-Pad141)") (class "Default")
      (node (ref "U1") (pin "141") (pinfunction "RESERVED_141") (pintype "passive+no_connect"))
    )
    (net (code "78") (name "unconnected-(U1-RESERVED-Pad142)") (class "Default")
      (node (ref "U1") (pin "142") (pinfunction "RESERVED_142") (pintype "passive+no_connect"))
    )
    (net (code "79") (name "unconnected-(U1-RESERVED-Pad143)") (class "Default")
      (node (ref "U1") (pin "143") (pinfunction "RESERVED_143") (pintype "passive+no_connect"))
    )
    (net (code "80") (name "unconnected-(U1-RESERVED-Pad144)") (class "Default")
      (node (ref "U1") (pin "144") (pinfunction "RESERVED_144") (pintype "passive+no_connect"))
    )
    (net (code "81") (name "unconnected-(U1-SDIO1_CMD-Pad33)") (class "Default")
      (node (ref "U1") (pin "33") (pinfunction "SDIO1_CMD_33") (pintype "passive+no_connect"))
    )
    (net (code "82") (name "unconnected-(U1-SDIO1_DATA0-Pad31)") (class "Default")
      (node (ref "U1") (pin "31") (pinfunction "SDIO1_DATA0_31") (pintype "passive+no_connect"))
    )
    (net (code "83") (name "unconnected-(U1-SDIO1_DATA1-Pad30)") (class "Default")
      (node (ref "U1") (pin "30") (pinfunction "SDIO1_DATA1_30") (pintype "passive+no_connect"))
    )
    (net (code "84") (name "unconnected-(U1-SDIO1_DATA2-Pad29)") (class "Default")
      (node (ref "U1") (pin "29") (pinfunction "SDIO1_DATA2_29") (pintype "passive+no_connect"))
    )
    (net (code "85") (name "unconnected-(U1-SDIO1_DATA3-Pad28)") (class "Default")
      (node (ref "U1") (pin "28") (pinfunction "SDIO1_DATA3_28") (pintype "passive+no_connect"))
    )
    (net (code "86") (name "unconnected-(U1-SDIO1_VDD-Pad34)") (class "Default")
      (node (ref "U1") (pin "34") (pinfunction "SDIO1_VDD_34") (pintype "passive+no_connect"))
    )
    (net (code "87") (name "unconnected-(U1-SDIO2_CLK-Pad133)") (class "Default")
      (node (ref "U1") (pin "133") (pinfunction "SDIO2_CLK_133") (pintype "passive+no_connect"))
    )
    (net (code "88") (name "unconnected-(U1-SDIO2_CMD-Pad134)") (class "Default")
      (node (ref "U1") (pin "134") (pinfunction "SDIO2_CMD_134") (pintype "passive+no_connect"))
    )
    (net (code "89") (name "unconnected-(U1-SDIO2_DATA0-Pad132)") (class "Default")
      (node (ref "U1") (pin "132") (pinfunction "SDIO2_DATA0_132") (pintype "passive+no_connect"))
    )
    (net (code "90") (name "unconnected-(U1-SDIO2_DATA1-Pad131)") (class "Default")
      (node (ref "U1") (pin "131") (pinfunction "SDIO2_DATA1_131") (pintype "passive+no_connect"))
    )
    (net (code "91") (name "unconnected-(U1-SDIO2_DATA2-Pad130)") (class "Default")
      (node (ref "U1") (pin "130") (pinfunction "SDIO2_DATA2_130") (pintype "passive+no_connect"))
    )
    (net (code "92") (name "unconnected-(U1-SDIO2_DATA3-Pad129)") (class "Default")
      (node (ref "U1") (pin "129") (pinfunction "SDIO2_DATA3_129") (pintype "passive+no_connect"))
    )
    (net (code "93") (name "unconnected-(U1-SD_DET-Pad23)") (class "Default")
      (node (ref "U1") (pin "23") (pinfunction "SD_DET_23") (pintype "passive+no_connect"))
    )
    (net (code "94") (name "unconnected-(U1-SPK_N-Pad123)") (class "Default")
      (node (ref "U1") (pin "123") (pinfunction "SPK_N_123") (pintype "passive+no_connect"))
    )
    (net (code "95") (name "unconnected-(U1-SPK_P-Pad124)") (class "Default")
      (node (ref "U1") (pin "124") (pinfunction "SPK_P_124") (pintype "passive+no_connect"))
    )
    (net (code "96") (name "unconnected-(U1-STATUS-Pad61)") (class "Default")
      (node (ref "U1") (pin "61") (pinfunction "STATUS_61") (pintype "passive+no_connect"))
    )
    (net (code "97") (name "unconnected-(U1-USB_BOOT-Pad115)") (class "Default")
      (node (ref "U1") (pin "115") (pinfunction "USB_BOOT_115") (pintype "passive+no_connect"))
    )
    (net (code "98") (name "unconnected-(U1-USB_DM-Pad70)") (class "Default")
      (node (ref "U1") (pin "70") (pinfunction "USB_DM_70") (pintype "passive+no_connect"))
    )
    (net (code "99") (name "unconnected-(U1-USB_DP-Pad69)") (class "Default")
      (node (ref "U1") (pin "69") (pinfunction "USB_DP_69") (pintype "passive+no_connect"))
    )
    (net (code "100") (name "unconnected-(U1-USB_VBUS-Pad71)") (class "Default")
      (node (ref "U1") (pin "71") (pinfunction "USB_VBUS_71") (pintype "passive+no_connect"))
    )
    (net (code "101") (name "unconnected-(U1-USIM_DET-Pad13)") (class "Default")
      (node (ref "U1") (pin "13") (pinfunction "USIM_DET_13") (pintype "passive+no_connect"))
    )
    (net (code "102") (name "unconnected-(U1-WAKEUP_IN-Pad1)") (class "Default")
      (node (ref "U1") (pin "1") (pinfunction "WAKEUP_IN_1") (pintype "passive+no_connect"))
    )
    (net (code "103") (name "unconnected-(U1-WLAN_EN-Pad136)") (class "Default")
      (node (ref "U1") (pin "136") (pinfunction "WLAN_EN_136") (pintype "passive+no_connect"))
    )
    (net (code "104") (name "unconnected-(U1-WLAN_PWR__EN-Pad127)") (class "Default")
      (node (ref "U1") (pin "127") (pinfunction "WLAN_PWR__EN_127") (pintype "passive+no_connect"))
    )
    (net (code "105") (name "unconnected-(U1-WLAN_SLP__CLK-Pad118)") (class "Default")
      (node (ref "U1") (pin "118") (pinfunction "WLAN_SLP__CLK_118") (pintype "passive+no_connect"))
    )
    (net (code "106") (name "unconnected-(U1-WLAN_WAKE-Pad135)") (class "Default")
      (node (ref "U1") (pin "135") (pinfunction "WLAN_WAKE_135") (pintype "passive+no_connect"))
    )
    (net (code "107") (name "unconnected-(U1-W_DISABLE#-Pad4)") (class "Default")
      (node (ref "U1") (pin "4") (pinfunction "W_DISABLE#_4") (pintype "passive+no_connect"))
    )
  )
)
